# battery_buzzer.net
KiCad netlist of a schematic drawn in EAGLE
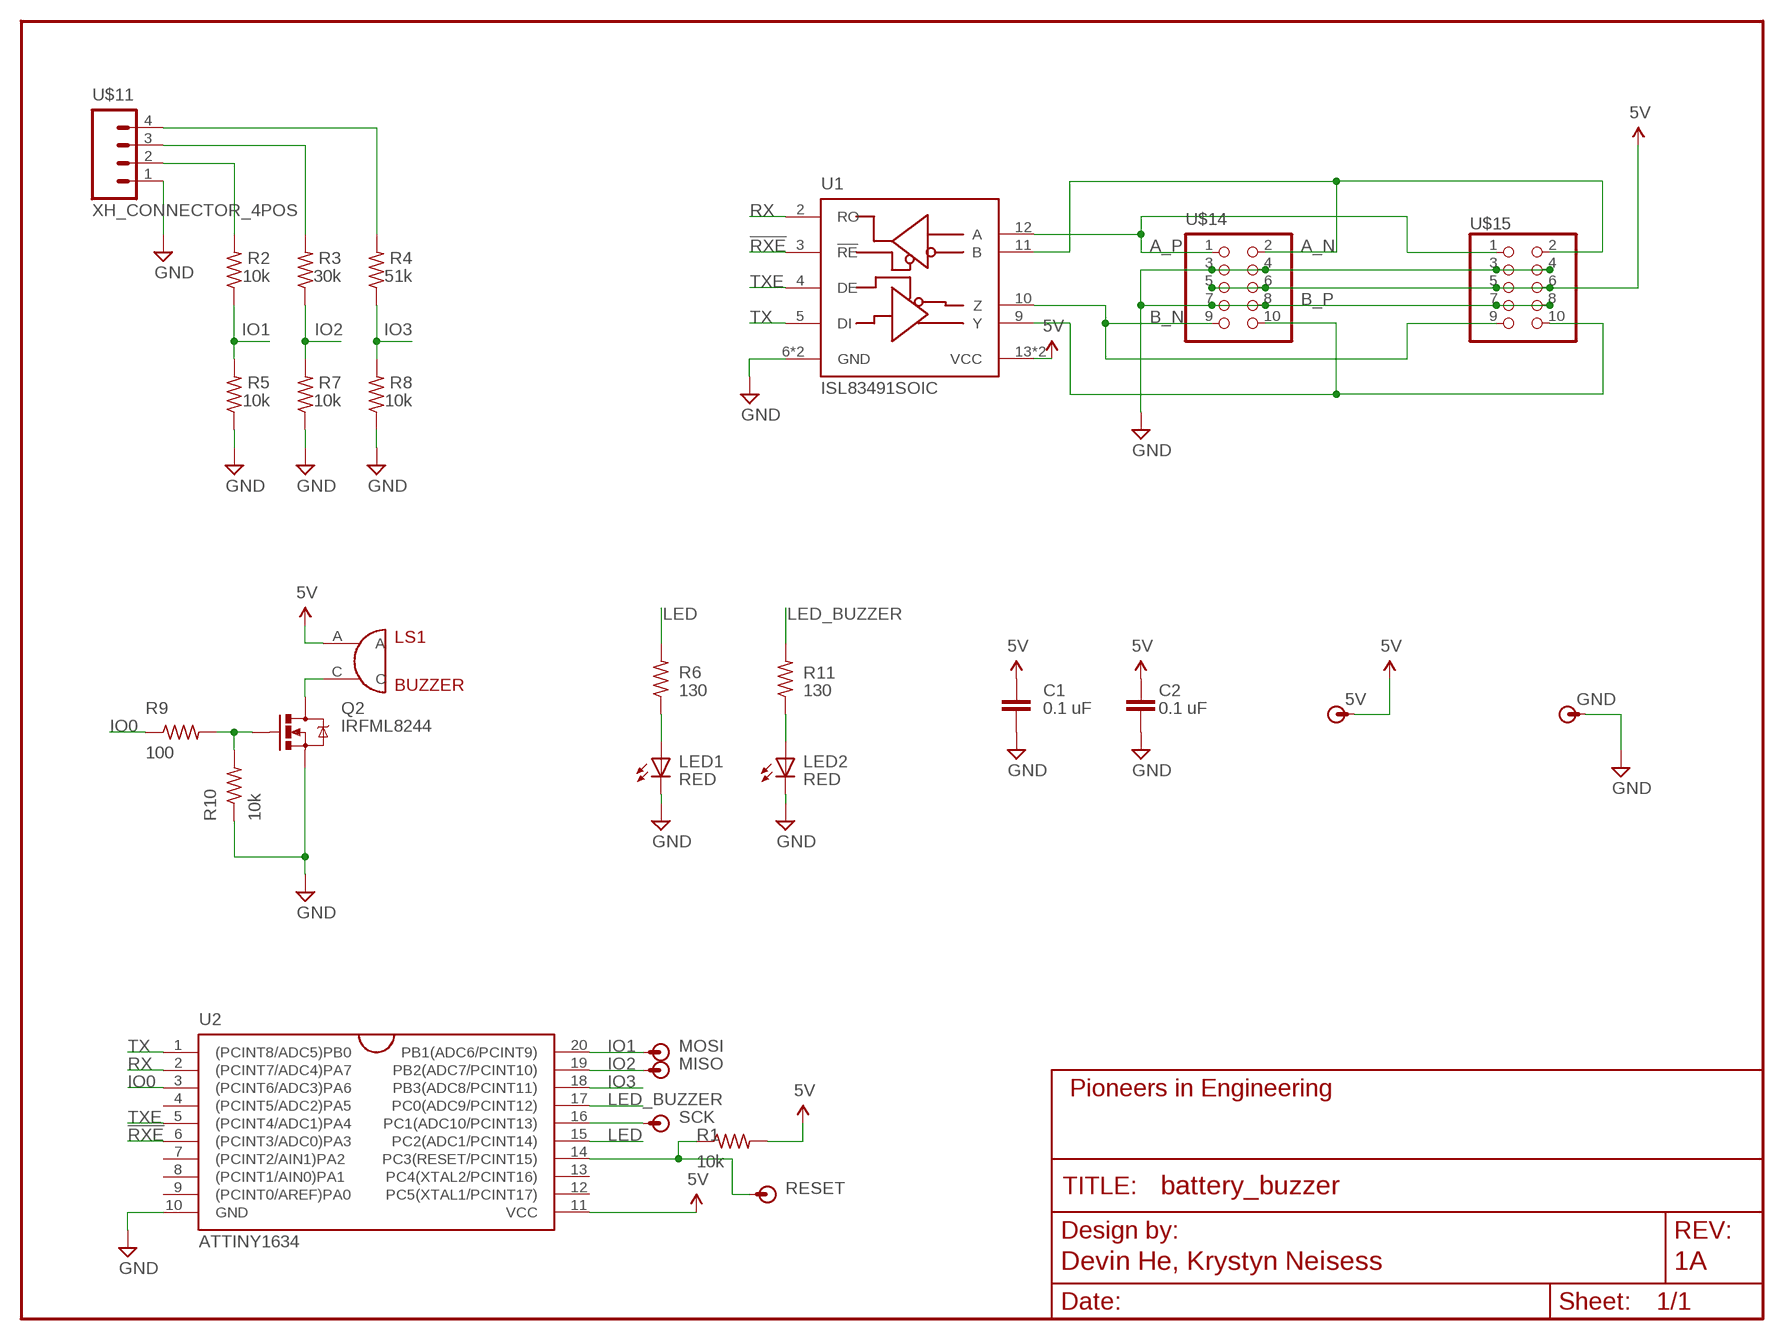
[diagram p0: schematic, sheet 1]

(export (version "E")
  (design (tool "Eeschema 10.0.6"))
  (components
    (comp (ref "5V")
      (value "POGO_PIN")
      (footprint "eagle-import:POGO_PIN_394")
      (libsource (lib "eagle-import") (part "POGO_PIN"))
    )
    (comp (ref "C1")
      (value "0.1 uF")
      (footprint "eagle-import:0603-CAP")
      (libsource (lib "eagle-import") (part "CAP0603-CAP"))
    )
    (comp (ref "C2")
      (value "0.1 uF")
      (footprint "eagle-import:0603-CAP")
      (libsource (lib "eagle-import") (part "CAP0603-CAP"))
    )
    (comp (ref "GND")
      (value "POGO_PIN")
      (footprint "eagle-import:POGO_PIN_394")
      (libsource (lib "eagle-import") (part "POGO_PIN"))
    )
    (comp (ref "LED1")
      (value "RED")
      (footprint "eagle-import:LED-0805")
      (libsource (lib "eagle-import") (part "LED0805"))
    )
    (comp (ref "LED2")
      (value "RED")
      (footprint "eagle-import:LED-0805")
      (libsource (lib "eagle-import") (part "LED0805"))
    )
    (comp (ref "LS1")
      (value "BUZZER")
      (footprint "eagle-import:BUZZER_MAGNETIC_5V_12MM_RADIAL")
      (libsource (lib "eagle-import") (part "BUZZER"))
    )
    (comp (ref "MISO")
      (value "POGO_PIN")
      (footprint "eagle-import:POGO_PIN_394")
      (libsource (lib "eagle-import") (part "POGO_PIN"))
    )
    (comp (ref "MOSI")
      (value "POGO_PIN")
      (footprint "eagle-import:POGO_PIN_394")
      (libsource (lib "eagle-import") (part "POGO_PIN"))
    )
    (comp (ref "Q2")
      (value "IRFML8244")
      (footprint "eagle-import:SOT23-3")
      (libsource (lib "eagle-import") (part "MOSFET-NCHANNELSMD"))
    )
    (comp (ref "R1")
      (value "10k")
      (footprint "eagle-import:R0603")
      (libsource (lib "eagle-import") (part "R-US_R0603"))
    )
    (comp (ref "R2")
      (value "10k")
      (footprint "eagle-import:R0603")
      (libsource (lib "eagle-import") (part "R-US_R0603"))
    )
    (comp (ref "R3")
      (value "30k")
      (footprint "eagle-import:R0603")
      (libsource (lib "eagle-import") (part "R-US_R0603"))
    )
    (comp (ref "R4")
      (value "51k")
      (footprint "eagle-import:R0603")
      (libsource (lib "eagle-import") (part "R-US_R0603"))
    )
    (comp (ref "R5")
      (value "10k")
      (footprint "eagle-import:R0603")
      (libsource (lib "eagle-import") (part "R-US_R0603"))
    )
    (comp (ref "R6")
      (value "130")
      (footprint "eagle-import:R0603")
      (libsource (lib "eagle-import") (part "R-US_R0603"))
    )
    (comp (ref "R7")
      (value "10k")
      (footprint "eagle-import:R0603")
      (libsource (lib "eagle-import") (part "R-US_R0603"))
    )
    (comp (ref "R8")
      (value "10k")
      (footprint "eagle-import:R0603")
      (libsource (lib "eagle-import") (part "R-US_R0603"))
    )
    (comp (ref "R9")
      (value "100")
      (footprint "eagle-import:R0603")
      (libsource (lib "eagle-import") (part "R-US_R0603"))
    )
    (comp (ref "R10")
      (value "10k")
      (footprint "eagle-import:R0603")
      (libsource (lib "eagle-import") (part "R-US_R0603"))
    )
    (comp (ref "R11")
      (value "130")
      (footprint "eagle-import:R0603")
      (libsource (lib "eagle-import") (part "R-US_R0603"))
    )
    (comp (ref "RESET")
      (value "POGO_PIN")
      (footprint "eagle-import:POGO_PIN_394")
      (libsource (lib "eagle-import") (part "POGO_PIN"))
    )
    (comp (ref "SCK")
      (value "POGO_PIN")
      (footprint "eagle-import:POGO_PIN_394")
      (libsource (lib "eagle-import") (part "POGO_PIN"))
    )
    (comp (ref "U$11")
      (value "XH_CONNECTOR_4POS")
      (footprint "eagle-import:XH_CONNECTOR_4POS_2.5MM")
      (libsource (lib "eagle-import") (part "XH_CONNECTOR_4POS"))
    )
    (comp (ref "U$14")
      (value "SENSOR_CON_5PINPTH-SHROUDED")
      (footprint "eagle-import:2X5_SHROUDED")
      (libsource (lib "eagle-import") (part "SENSOR_CON_5PINPTH-SHROUDED"))
    )
    (comp (ref "U$15")
      (value "SENSOR_CON_5PINSMD-EDGE")
      (footprint "eagle-import:2X5-EDGE")
      (libsource (lib "eagle-import") (part "SENSOR_CON_5PINSMD-EDGE"))
    )
    (comp (ref "U1")
      (value "ISL83491SOIC")
      (footprint "eagle-import:SOIC14")
      (libsource (lib "eagle-import") (part "ISL83491SOIC"))
    )
    (comp (ref "U2")
      (value "ATTINY1634")
      (footprint "eagle-import:SOIC20")
      (libsource (lib "eagle-import") (part "ATTINY1634"))
    )
  )
  (nets
    (net (code "1") (name "/A_N") (class "Default")
      (node (ref "U$14") (pin "2") (pinfunction "2_2") (pintype "passive"))
      (node (ref "U$15") (pin "2") (pinfunction "2_2") (pintype "passive"))
      (node (ref "U1") (pin "11") (pinfunction "B_11") (pintype "bidirectional"))
    )
    (net (code "2") (name "/A_P") (class "Default")
      (node (ref "U$14") (pin "1") (pinfunction "1_1") (pintype "passive"))
      (node (ref "U$15") (pin "1") (pinfunction "1_1") (pintype "passive"))
      (node (ref "U1") (pin "12") (pinfunction "A_12") (pintype "bidirectional"))
    )
    (net (code "3") (name "/B_N") (class "Default")
      (node (ref "U$14") (pin "9") (pinfunction "9_9") (pintype "passive"))
      (node (ref "U$15") (pin "9") (pinfunction "9_9") (pintype "passive"))
      (node (ref "U1") (pin "10") (pinfunction "Z_10") (pintype "bidirectional"))
    )
    (net (code "4") (name "/B_P") (class "Default")
      (node (ref "U$14") (pin "10") (pinfunction "10_10") (pintype "passive"))
      (node (ref "U$15") (pin "10") (pinfunction "10_10") (pintype "passive"))
      (node (ref "U1") (pin "9") (pinfunction "Y_9") (pintype "bidirectional"))
    )
    (net (code "5") (name "/IO0") (class "Default")
      (node (ref "R9") (pin "1") (pinfunction "1_1") (pintype "passive"))
      (node (ref "U2") (pin "3") (pinfunction "(PCINT6/ADC3)PA6_3") (pintype "bidirectional"))
    )
    (net (code "6") (name "/IO1") (class "Default")
      (node (ref "MOSI") (pin "POGO_PIN") (pinfunction "P$1_POGO_PIN") (pintype "bidirectional"))
      (node (ref "R2") (pin "1") (pinfunction "1_1") (pintype "passive"))
      (node (ref "R5") (pin "2") (pinfunction "2_2") (pintype "passive"))
      (node (ref "U2") (pin "20") (pinfunction "PB1(ADC6/PCINT9)_20") (pintype "bidirectional"))
    )
    (net (code "7") (name "/IO2") (class "Default")
      (node (ref "MISO") (pin "POGO_PIN") (pinfunction "P$1_POGO_PIN") (pintype "bidirectional"))
      (node (ref "R3") (pin "1") (pinfunction "1_1") (pintype "passive"))
      (node (ref "R7") (pin "2") (pinfunction "2_2") (pintype "passive"))
      (node (ref "U2") (pin "19") (pinfunction "PB2(ADC7/PCINT10)_19") (pintype "bidirectional"))
    )
    (net (code "8") (name "/IO3") (class "Default")
      (node (ref "R4") (pin "1") (pinfunction "1_1") (pintype "passive"))
      (node (ref "R8") (pin "2") (pinfunction "2_2") (pintype "passive"))
      (node (ref "U2") (pin "18") (pinfunction "PB3(ADC8/PCINT11)_18") (pintype "bidirectional"))
    )
    (net (code "9") (name "/LED") (class "Default")
      (node (ref "R6") (pin "2") (pinfunction "2_2") (pintype "passive"))
      (node (ref "U2") (pin "15") (pinfunction "PC2(ADC1/PCINT14)_15") (pintype "bidirectional"))
    )
    (net (code "10") (name "/LED_BUZZER") (class "Default")
      (node (ref "R11") (pin "2") (pinfunction "2_2") (pintype "passive"))
      (node (ref "U2") (pin "17") (pinfunction "PC0(ADC9/PCINT12)_17") (pintype "bidirectional"))
    )
    (net (code "11") (name "/RX") (class "Default")
      (node (ref "U1") (pin "2") (pinfunction "RO_2") (pintype "bidirectional"))
      (node (ref "U2") (pin "2") (pinfunction "(PCINT7/ADC4)PA7_2") (pintype "bidirectional"))
    )
    (net (code "12") (name "/TX") (class "Default")
      (node (ref "U1") (pin "5") (pinfunction "DI_5") (pintype "bidirectional"))
      (node (ref "U2") (pin "1") (pinfunction "(PCINT8/ADC5)PB0_1") (pintype "bidirectional"))
    )
    (net (code "13") (name "/TXE") (class "Default")
      (node (ref "U1") (pin "4") (pinfunction "DE_4") (pintype "bidirectional"))
      (node (ref "U2") (pin "5") (pinfunction "(PCINT4/ADC1)PA4_5") (pintype "bidirectional"))
    )
    (net (code "14") (name "/~{RXE}") (class "Default")
      (node (ref "U1") (pin "3") (pinfunction "~{RE}_3") (pintype "bidirectional"))
      (node (ref "U2") (pin "6") (pinfunction "(PCINT3/ADC0)PA3_6") (pintype "bidirectional"))
    )
    (net (code "15") (name "5V") (class "Default")
      (node (ref "5V") (pin "POGO_PIN") (pinfunction "P$1_POGO_PIN") (pintype "bidirectional"))
      (node (ref "C1") (pin "1") (pinfunction "1_1") (pintype "passive"))
      (node (ref "C2") (pin "1") (pinfunction "1_1") (pintype "passive"))
      (node (ref "LS1") (pin "A") (pinfunction "A_A") (pintype "bidirectional"))
      (node (ref "R1") (pin "2") (pinfunction "2_2") (pintype "passive"))
      (node (ref "U$14") (pin "5") (pinfunction "5_5") (pintype "passive"))
      (node (ref "U$14") (pin "6") (pinfunction "6_6") (pintype "passive"))
      (node (ref "U$15") (pin "5") (pinfunction "5_5") (pintype "passive"))
      (node (ref "U$15") (pin "6") (pinfunction "6_6") (pintype "passive"))
      (node (ref "U1") (pin "13") (pinfunction "VCC_13") (pintype "bidirectional"))
      (node (ref "U1") (pin "14") (pinfunction "VCC_14") (pintype "bidirectional"))
      (node (ref "U2") (pin "11") (pinfunction "VCC_11") (pintype "bidirectional"))
    )
    (net (code "16") (name "GND") (class "Default")
      (node (ref "C1") (pin "2") (pinfunction "2_2") (pintype "passive"))
      (node (ref "C2") (pin "2") (pinfunction "2_2") (pintype "passive"))
      (node (ref "GND") (pin "POGO_PIN") (pinfunction "P$1_POGO_PIN") (pintype "bidirectional"))
      (node (ref "LED1") (pin "C") (pinfunction "C_C") (pintype "passive"))
      (node (ref "LED2") (pin "C") (pinfunction "C_C") (pintype "passive"))
      (node (ref "Q2") (pin "2") (pinfunction "S_2") (pintype "passive"))
      (node (ref "R10") (pin "1") (pinfunction "1_1") (pintype "passive"))
      (node (ref "R5") (pin "1") (pinfunction "1_1") (pintype "passive"))
      (node (ref "R7") (pin "1") (pinfunction "1_1") (pintype "passive"))
      (node (ref "R8") (pin "1") (pinfunction "1_1") (pintype "passive"))
      (node (ref "U$11") (pin "1") (pinfunction "1_1") (pintype "passive"))
      (node (ref "U$14") (pin "3") (pinfunction "3_3") (pintype "passive"))
      (node (ref "U$14") (pin "4") (pinfunction "4_4") (pintype "passive"))
      (node (ref "U$14") (pin "7") (pinfunction "7_7") (pintype "passive"))
      (node (ref "U$14") (pin "8") (pinfunction "8_8") (pintype "passive"))
      (node (ref "U$15") (pin "3") (pinfunction "3_3") (pintype "passive"))
      (node (ref "U$15") (pin "4") (pinfunction "4_4") (pintype "passive"))
      (node (ref "U$15") (pin "7") (pinfunction "7_7") (pintype "passive"))
      (node (ref "U$15") (pin "8") (pinfunction "8_8") (pintype "passive"))
      (node (ref "U1") (pin "6") (pinfunction "GND_6") (pintype "bidirectional"))
      (node (ref "U1") (pin "7") (pinfunction "GND_7") (pintype "bidirectional"))
      (node (ref "U2") (pin "10") (pinfunction "GND_10") (pintype "bidirectional"))
    )
    (net (code "17") (name "Net-(LED1-PadA)") (class "Default")
      (node (ref "LED1") (pin "A") (pinfunction "A_A") (pintype "passive"))
      (node (ref "R6") (pin "1") (pinfunction "1_1") (pintype "passive"))
    )
    (net (code "18") (name "Net-(LED2-PadA)") (class "Default")
      (node (ref "LED2") (pin "A") (pinfunction "A_A") (pintype "passive"))
      (node (ref "R11") (pin "1") (pinfunction "1_1") (pintype "passive"))
    )
    (net (code "19") (name "Net-(Q2-D)") (class "Default")
      (node (ref "LS1") (pin "C") (pinfunction "C_C") (pintype "bidirectional"))
      (node (ref "Q2") (pin "3") (pinfunction "D_3") (pintype "passive"))
    )
    (net (code "20") (name "Net-(Q2-G)") (class "Default")
      (node (ref "Q2") (pin "1") (pinfunction "G_1") (pintype "passive"))
      (node (ref "R10") (pin "2") (pinfunction "2_2") (pintype "passive"))
      (node (ref "R9") (pin "2") (pinfunction "2_2") (pintype "passive"))
    )
    (net (code "21") (name "Net-(R2-Pad2)") (class "Default")
      (node (ref "R2") (pin "2") (pinfunction "2_2") (pintype "passive"))
      (node (ref "U$11") (pin "2") (pinfunction "2_2") (pintype "passive"))
    )
    (net (code "22") (name "Net-(R3-Pad2)") (class "Default")
      (node (ref "R3") (pin "2") (pinfunction "2_2") (pintype "passive"))
      (node (ref "U$11") (pin "3") (pinfunction "3_3") (pintype "passive"))
    )
    (net (code "23") (name "Net-(R4-Pad2)") (class "Default")
      (node (ref "R4") (pin "2") (pinfunction "2_2") (pintype "passive"))
      (node (ref "U$11") (pin "4") (pinfunction "4_4") (pintype "passive"))
    )
    (net (code "24") (name "Net-(RESET-P$1)") (class "Default")
      (node (ref "R1") (pin "1") (pinfunction "1_1") (pintype "passive"))
      (node (ref "RESET") (pin "POGO_PIN") (pinfunction "P$1_POGO_PIN") (pintype "bidirectional"))
      (node (ref "U2") (pin "14") (pinfunction "PC3(RESET/PCINT15)_14") (pintype "bidirectional"))
    )
    (net (code "25") (name "Net-(SCK-P$1)") (class "Default")
      (node (ref "SCK") (pin "POGO_PIN") (pinfunction "P$1_POGO_PIN") (pintype "bidirectional"))
      (node (ref "U2") (pin "16") (pinfunction "PC1(ADC10/PCINT13)_16") (pintype "bidirectional"))
    )
    (net (code "26") (name "unconnected-(U2-(PCINT0{slash}AREF)PA0-Pad9)") (class "Default")
      (node (ref "U2") (pin "9") (pinfunction "(PCINT0/AREF)PA0_9") (pintype "bidirectional"))
    )
    (net (code "27") (name "unconnected-(U2-(PCINT1{slash}AIN0)PA1-Pad8)") (class "Default")
      (node (ref "U2") (pin "8") (pinfunction "(PCINT1/AIN0)PA1_8") (pintype "bidirectional"))
    )
    (net (code "28") (name "unconnected-(U2-(PCINT2{slash}AIN1)PA2-Pad7)") (class "Default")
      (node (ref "U2") (pin "7") (pinfunction "(PCINT2/AIN1)PA2_7") (pintype "bidirectional"))
    )
    (net (code "29") (name "unconnected-(U2-(PCINT5{slash}ADC2)PA5-Pad4)") (class "Default")
      (node (ref "U2") (pin "4") (pinfunction "(PCINT5/ADC2)PA5_4") (pintype "bidirectional"))
    )
    (net (code "30") (name "unconnected-(U2-PC4(XTAL2{slash}PCINT16)-Pad13)") (class "Default")
      (node (ref "U2") (pin "13") (pinfunction "PC4(XTAL2/PCINT16)_13") (pintype "bidirectional"))
    )
    (net (code "31") (name "unconnected-(U2-PC5(XTAL1{slash}PCINT17)-Pad12)") (class "Default")
      (node (ref "U2") (pin "12") (pinfunction "PC5(XTAL1/PCINT17)_12") (pintype "bidirectional"))
    )
  )
)
